# nrf52_breakout_rev_1.net
KiCad netlist of a schematic drawn in EAGLE
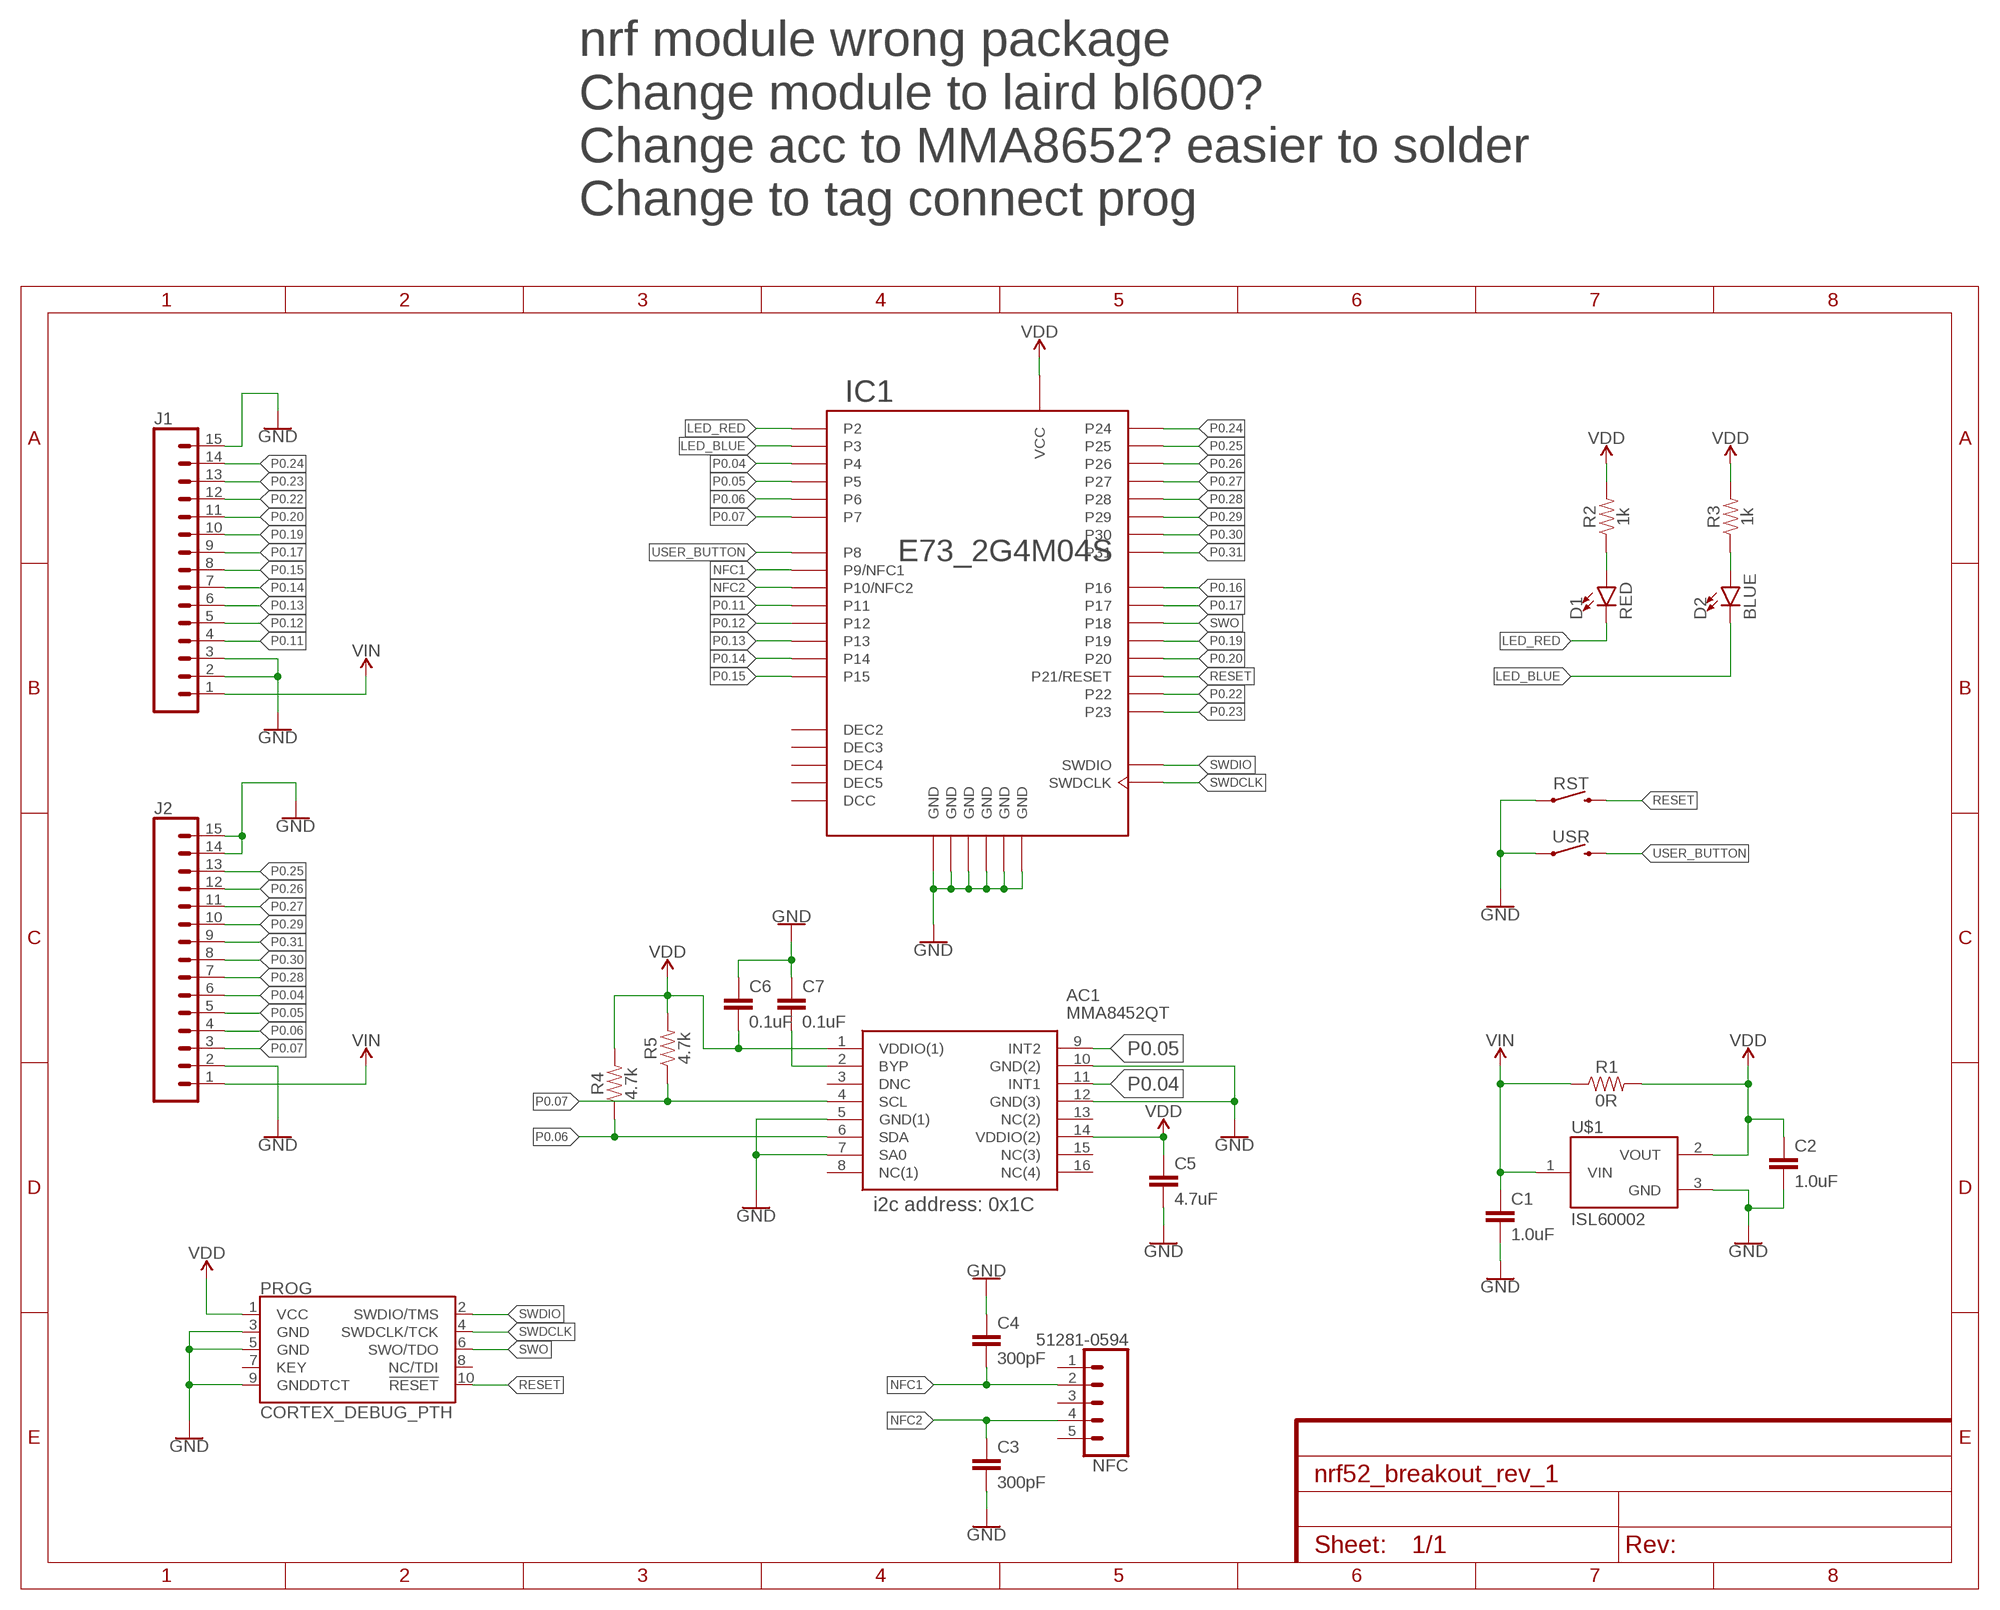
[diagram p0: schematic, sheet 1]

(export (version "E")
  (design (tool "Eeschema 10.0.6"))
  (components
    (comp (ref "AC1")
      (value "MMA8452QT")
      (footprint "eagle-import:PQFN50P300X300X100-16N")
      (fields (field (name "RS_PART_NUMBER") "9227526"))
      (libsource (lib "eagle-import") (part "MMA8452QT"))
    )
    (comp (ref "C1")
      (value "1.0uF")
      (footprint "eagle-import:0603")
      (libsource (lib "eagle-import") (part "1.0UF-0603-16V-10%"))
    )
    (comp (ref "C2")
      (value "1.0uF")
      (footprint "eagle-import:0603")
      (libsource (lib "eagle-import") (part "1.0UF-0603-16V-10%"))
    )
    (comp (ref "C3")
      (value "300pF")
      (footprint "eagle-import:0402")
      (libsource (lib "eagle-import") (part "470NF-0402-16V-10%"))
    )
    (comp (ref "C4")
      (value "300pF")
      (footprint "eagle-import:0402")
      (libsource (lib "eagle-import") (part "470NF-0402-16V-10%"))
    )
    (comp (ref "C5")
      (value "4.7uF")
      (footprint "eagle-import:0603")
      (libsource (lib "eagle-import") (part "4.7UF0603"))
    )
    (comp (ref "C6")
      (value "0.1uF")
      (footprint "eagle-import:0402")
      (libsource (lib "eagle-import") (part "0.1UF-0402-16V-10%"))
    )
    (comp (ref "C7")
      (value "0.1uF")
      (footprint "eagle-import:0402")
      (libsource (lib "eagle-import") (part "0.1UF-0402-16V-10%"))
    )
    (comp (ref "D1")
      (value "RED")
      (footprint "eagle-import:LED-0603")
      (libsource (lib "eagle-import") (part "LED-RED0603"))
    )
    (comp (ref "D2")
      (value "BLUE")
      (footprint "eagle-import:LED-0603")
      (libsource (lib "eagle-import") (part "LED-BLUE0603"))
    )
    (comp (ref "IC1")
      (value "E73_2G4M04S")
      (footprint "eagle-import:E73_2G4M04S")
      (libsource (lib "eagle-import") (part "E73_2G4M04S"))
    )
    (comp (ref "J1")
      (value "CONN_15")
      (footprint "eagle-import:1X15")
      (libsource (lib "eagle-import") (part "CONN_15"))
    )
    (comp (ref "J2")
      (value "CONN_15")
      (footprint "eagle-import:1X15")
      (libsource (lib "eagle-import") (part "CONN_15"))
    )
    (comp (ref "NFC")
      (value "51281-0594")
      (footprint "eagle-import:51281-0594")
      (libsource (lib "eagle-import") (part "51281-0594"))
    )
    (comp (ref "PROG")
      (value "CORTEX_DEBUG_PTH")
      (footprint "eagle-import:2X5-PTH-1.27MM")
      (libsource (lib "eagle-import") (part "CORTEX_DEBUG_PTH"))
    )
    (comp (ref "R1")
      (value "0R")
      (footprint "eagle-import:0603")
      (libsource (lib "eagle-import") (part "RESISTOR0603"))
    )
    (comp (ref "R2")
      (value "1k")
      (footprint "eagle-import:0603")
      (libsource (lib "eagle-import") (part "RESISTOR0603"))
    )
    (comp (ref "R3")
      (value "1k")
      (footprint "eagle-import:0603")
      (libsource (lib "eagle-import") (part "RESISTOR0603"))
    )
    (comp (ref "R4")
      (value "4.7k")
      (footprint "eagle-import:0402")
      (libsource (lib "eagle-import") (part "RESISTOR0402"))
    )
    (comp (ref "R5")
      (value "4.7k")
      (footprint "eagle-import:0402")
      (libsource (lib "eagle-import") (part "RESISTOR0402"))
    )
    (comp (ref "RST")
      (value "MOMENTARY-SWITCH-SPST-SMD-4.6X2.8MM")
      (footprint "eagle-import:TACTILE_SWITCH_SMD_4.6X2.8MM")
      (libsource (lib "eagle-import") (part "MOMENTARY-SWITCH-SPST-SMD-4.6X2.8MM"))
    )
    (comp (ref "U$1")
      (value "ISL60002")
      (footprint "eagle-import:SOT23-3")
      (libsource (lib "eagle-import") (part "ISL60002"))
    )
    (comp (ref "USR")
      (value "MOMENTARY-SWITCH-SPST-SMD-4.6X2.8MM")
      (footprint "eagle-import:TACTILE_SWITCH_SMD_4.6X2.8MM")
      (libsource (lib "eagle-import") (part "MOMENTARY-SWITCH-SPST-SMD-4.6X2.8MM"))
    )
  )
  (nets
    (net (code "1") (name "/DCC") (class "Default")
      (node (ref "IC1") (pin "13") (pinfunction "DCC_13") (pintype "power_in"))
    )
    (net (code "2") (name "/DEC2") (class "Default")
      (node (ref "IC1") (pin "3") (pinfunction "DEC2_3") (pintype "power_in"))
    )
    (net (code "3") (name "/DEC3") (class "Default")
      (node (ref "IC1") (pin "4") (pinfunction "DEC3_4") (pintype "power_in"))
    )
    (net (code "4") (name "/DEC4") (class "Default")
      (node (ref "IC1") (pin "12") (pinfunction "DEC4_12") (pintype "power_in"))
    )
    (net (code "5") (name "/DEC5") (class "Default")
      (node (ref "IC1") (pin "14") (pinfunction "DEC5_14") (pintype "power_in"))
    )
    (net (code "6") (name "GND") (class "Default")
      (node (ref "AC1") (pin "10") (pinfunction "GND(2)_10") (pintype "input"))
      (node (ref "AC1") (pin "12") (pinfunction "GND(3)_12") (pintype "input"))
      (node (ref "AC1") (pin "5") (pinfunction "GND(1)_5") (pintype "input"))
      (node (ref "AC1") (pin "7") (pinfunction "SA0_7") (pintype "input"))
      (node (ref "C1") (pin "2") (pinfunction "2_2") (pintype "passive"))
      (node (ref "C2") (pin "2") (pinfunction "2_2") (pintype "passive"))
      (node (ref "C3") (pin "2") (pinfunction "2_2") (pintype "passive"))
      (node (ref "C4") (pin "1") (pinfunction "1_1") (pintype "passive"))
      (node (ref "C5") (pin "2") (pinfunction "2_2") (pintype "passive"))
      (node (ref "C6") (pin "1") (pinfunction "1_1") (pintype "passive"))
      (node (ref "C7") (pin "1") (pinfunction "1_1") (pintype "passive"))
      (node (ref "IC1") (pin "0") (pinfunction "GND_0") (pintype "bidirectional"))
      (node (ref "IC1") (pin "1") (pinfunction "GND_1") (pintype "bidirectional"))
      (node (ref "IC1") (pin "15") (pinfunction "GND_15") (pintype "bidirectional"))
      (node (ref "IC1") (pin "2") (pinfunction "GND_2") (pintype "bidirectional"))
      (node (ref "IC1") (pin "42") (pinfunction "GND_42") (pintype "bidirectional"))
      (node (ref "IC1") (pin "43") (pinfunction "GND_43") (pintype "bidirectional"))
      (node (ref "J1") (pin "15") (pinfunction "15_15") (pintype "passive"))
      (node (ref "J1") (pin "2") (pinfunction "2_2") (pintype "passive"))
      (node (ref "J1") (pin "3") (pinfunction "3_3") (pintype "passive"))
      (node (ref "J2") (pin "14") (pinfunction "14_14") (pintype "passive"))
      (node (ref "J2") (pin "15") (pinfunction "15_15") (pintype "passive"))
      (node (ref "J2") (pin "2") (pinfunction "2_2") (pintype "passive"))
      (node (ref "PROG") (pin "3") (pinfunction "GND_3") (pintype "bidirectional"))
      (node (ref "PROG") (pin "5") (pinfunction "GND_5") (pintype "bidirectional"))
      (node (ref "PROG") (pin "9") (pinfunction "GNDDTCT_9") (pintype "bidirectional"))
      (node (ref "RST") (pin "1") (pinfunction "1_1") (pintype "passive"))
      (node (ref "RST") (pin "2") (pinfunction "1_2") (pintype "passive"))
      (node (ref "U$1") (pin "3") (pinfunction "GND_3") (pintype "bidirectional"))
      (node (ref "USR") (pin "1") (pinfunction "1_1") (pintype "passive"))
      (node (ref "USR") (pin "2") (pinfunction "1_2") (pintype "passive"))
    )
    (net (code "7") (name "LED_BLUE") (class "Default")
      (node (ref "D2") (pin "C") (pinfunction "C_C") (pintype "passive"))
      (node (ref "IC1") (pin "18") (pinfunction "P3_18") (pintype "bidirectional"))
    )
    (net (code "8") (name "LED_RED") (class "Default")
      (node (ref "D1") (pin "C") (pinfunction "C_C") (pintype "passive"))
      (node (ref "IC1") (pin "17") (pinfunction "P2_17") (pintype "bidirectional"))
    )
    (net (code "9") (name "NFC1") (class "Default")
      (node (ref "C4") (pin "2") (pinfunction "2_2") (pintype "passive"))
      (node (ref "IC1") (pin "24") (pinfunction "P9/NFC1_24") (pintype "bidirectional"))
      (node (ref "NFC") (pin "2") (pinfunction "2_2") (pintype "passive"))
    )
    (net (code "10") (name "NFC2") (class "Default")
      (node (ref "C3") (pin "1") (pinfunction "1_1") (pintype "passive"))
      (node (ref "IC1") (pin "25") (pinfunction "P10/NFC2_25") (pintype "bidirectional"))
      (node (ref "NFC") (pin "4") (pinfunction "4_4") (pintype "passive"))
    )
    (net (code "11") (name "Net-(AC1-BYP)") (class "Default")
      (node (ref "AC1") (pin "2") (pinfunction "BYP_2") (pintype "input"))
      (node (ref "C7") (pin "2") (pinfunction "2_2") (pintype "passive"))
    )
    (net (code "12") (name "Net-(D1-PadA)") (class "Default")
      (node (ref "D1") (pin "A") (pinfunction "A_A") (pintype "passive"))
      (node (ref "R2") (pin "1") (pinfunction "1_1") (pintype "passive"))
    )
    (net (code "13") (name "Net-(D2-PadA)") (class "Default")
      (node (ref "D2") (pin "A") (pinfunction "A_A") (pintype "passive"))
      (node (ref "R3") (pin "1") (pinfunction "1_1") (pintype "passive"))
    )
    (net (code "14") (name "P0.04") (class "Default")
      (node (ref "AC1") (pin "11") (pinfunction "INT1_11") (pintype "input"))
      (node (ref "IC1") (pin "19") (pinfunction "P4_19") (pintype "bidirectional"))
      (node (ref "J2") (pin "6") (pinfunction "6_6") (pintype "passive"))
    )
    (net (code "15") (name "P0.05") (class "Default")
      (node (ref "AC1") (pin "9") (pinfunction "INT2_9") (pintype "input"))
      (node (ref "IC1") (pin "20") (pinfunction "P5_20") (pintype "bidirectional"))
      (node (ref "J2") (pin "5") (pinfunction "5_5") (pintype "passive"))
    )
    (net (code "16") (name "P0.06") (class "Default")
      (node (ref "AC1") (pin "6") (pinfunction "SDA_6") (pintype "input"))
      (node (ref "IC1") (pin "21") (pinfunction "P6_21") (pintype "bidirectional"))
      (node (ref "J2") (pin "4") (pinfunction "4_4") (pintype "passive"))
      (node (ref "R4") (pin "1") (pinfunction "1_1") (pintype "passive"))
    )
    (net (code "17") (name "P0.07") (class "Default")
      (node (ref "AC1") (pin "4") (pinfunction "SCL_4") (pintype "input"))
      (node (ref "IC1") (pin "22") (pinfunction "P7_22") (pintype "bidirectional"))
      (node (ref "J2") (pin "3") (pinfunction "3_3") (pintype "passive"))
      (node (ref "R5") (pin "1") (pinfunction "1_1") (pintype "passive"))
    )
    (net (code "18") (name "P0.11") (class "Default")
      (node (ref "IC1") (pin "26") (pinfunction "P11_26") (pintype "bidirectional"))
      (node (ref "J1") (pin "4") (pinfunction "4_4") (pintype "passive"))
    )
    (net (code "19") (name "P0.12") (class "Default")
      (node (ref "IC1") (pin "27") (pinfunction "P12_27") (pintype "bidirectional"))
      (node (ref "J1") (pin "5") (pinfunction "5_5") (pintype "passive"))
    )
    (net (code "20") (name "P0.13") (class "Default")
      (node (ref "IC1") (pin "28") (pinfunction "P13_28") (pintype "bidirectional"))
      (node (ref "J1") (pin "6") (pinfunction "6_6") (pintype "passive"))
    )
    (net (code "21") (name "P0.14") (class "Default")
      (node (ref "IC1") (pin "29") (pinfunction "P14_29") (pintype "bidirectional"))
      (node (ref "J1") (pin "7") (pinfunction "7_7") (pintype "passive"))
    )
    (net (code "22") (name "P0.15") (class "Default")
      (node (ref "IC1") (pin "30") (pinfunction "P15_30") (pintype "bidirectional"))
      (node (ref "J1") (pin "8") (pinfunction "8_8") (pintype "passive"))
    )
    (net (code "23") (name "P0.16") (class "Default")
      (node (ref "IC1") (pin "31") (pinfunction "P16_31") (pintype "bidirectional"))
    )
    (net (code "24") (name "P0.17") (class "Default")
      (node (ref "IC1") (pin "32") (pinfunction "P17_32") (pintype "bidirectional"))
      (node (ref "J1") (pin "9") (pinfunction "9_9") (pintype "passive"))
    )
    (net (code "25") (name "P0.19") (class "Default")
      (node (ref "IC1") (pin "34") (pinfunction "P19_34") (pintype "bidirectional"))
      (node (ref "J1") (pin "10") (pinfunction "10_10") (pintype "passive"))
    )
    (net (code "26") (name "P0.20") (class "Default")
      (node (ref "IC1") (pin "35") (pinfunction "P20_35") (pintype "bidirectional"))
      (node (ref "J1") (pin "11") (pinfunction "11_11") (pintype "passive"))
    )
    (net (code "27") (name "P0.22") (class "Default")
      (node (ref "IC1") (pin "39") (pinfunction "P22_39") (pintype "bidirectional"))
      (node (ref "J1") (pin "12") (pinfunction "12_12") (pintype "passive"))
    )
    (net (code "28") (name "P0.23") (class "Default")
      (node (ref "IC1") (pin "40") (pinfunction "P23_40") (pintype "bidirectional"))
      (node (ref "J1") (pin "13") (pinfunction "13_13") (pintype "passive"))
    )
    (net (code "29") (name "P0.24") (class "Default")
      (node (ref "IC1") (pin "41") (pinfunction "P24_41") (pintype "bidirectional"))
      (node (ref "J1") (pin "14") (pinfunction "14_14") (pintype "passive"))
    )
    (net (code "30") (name "P0.25") (class "Default")
      (node (ref "IC1") (pin "5") (pinfunction "P25_5") (pintype "bidirectional"))
      (node (ref "J2") (pin "13") (pinfunction "13_13") (pintype "passive"))
    )
    (net (code "31") (name "P0.26") (class "Default")
      (node (ref "IC1") (pin "6") (pinfunction "P26_6") (pintype "bidirectional"))
      (node (ref "J2") (pin "12") (pinfunction "12_12") (pintype "passive"))
    )
    (net (code "32") (name "P0.27") (class "Default")
      (node (ref "IC1") (pin "7") (pinfunction "P27_7") (pintype "bidirectional"))
      (node (ref "J2") (pin "11") (pinfunction "11_11") (pintype "passive"))
    )
    (net (code "33") (name "P0.28") (class "Default")
      (node (ref "IC1") (pin "8") (pinfunction "P28_8") (pintype "bidirectional"))
      (node (ref "J2") (pin "7") (pinfunction "7_7") (pintype "passive"))
    )
    (net (code "34") (name "P0.29") (class "Default")
      (node (ref "IC1") (pin "9") (pinfunction "P29_9") (pintype "bidirectional"))
      (node (ref "J2") (pin "10") (pinfunction "10_10") (pintype "passive"))
    )
    (net (code "35") (name "P0.30") (class "Default")
      (node (ref "IC1") (pin "10") (pinfunction "P30_10") (pintype "bidirectional"))
      (node (ref "J2") (pin "8") (pinfunction "8_8") (pintype "passive"))
    )
    (net (code "36") (name "P0.31") (class "Default")
      (node (ref "IC1") (pin "11") (pinfunction "P31_11") (pintype "bidirectional"))
      (node (ref "J2") (pin "9") (pinfunction "9_9") (pintype "passive"))
    )
    (net (code "37") (name "RESET") (class "Default")
      (node (ref "IC1") (pin "36") (pinfunction "P21/RESET_36") (pintype "bidirectional"))
      (node (ref "PROG") (pin "10") (pinfunction "~{RESET}_10") (pintype "bidirectional"))
      (node (ref "RST") (pin "3") (pinfunction "2_3") (pintype "passive"))
      (node (ref "RST") (pin "4") (pinfunction "2_4") (pintype "passive"))
    )
    (net (code "38") (name "SWDCLK") (class "Default")
      (node (ref "IC1") (pin "37") (pinfunction "SWDCLK_37") (pintype "input"))
      (node (ref "PROG") (pin "4") (pinfunction "SWDCLK/TCK_4") (pintype "bidirectional"))
    )
    (net (code "39") (name "SWDIO") (class "Default")
      (node (ref "IC1") (pin "38") (pinfunction "SWDIO_38") (pintype "bidirectional"))
      (node (ref "PROG") (pin "2") (pinfunction "SWDIO/TMS_2") (pintype "bidirectional"))
    )
    (net (code "40") (name "SWO") (class "Default")
      (node (ref "IC1") (pin "33") (pinfunction "P18_33") (pintype "bidirectional"))
      (node (ref "PROG") (pin "6") (pinfunction "SWO/TDO_6") (pintype "bidirectional"))
    )
    (net (code "41") (name "USER_BUTTON") (class "Default")
      (node (ref "IC1") (pin "23") (pinfunction "P8_23") (pintype "bidirectional"))
      (node (ref "USR") (pin "3") (pinfunction "2_3") (pintype "passive"))
      (node (ref "USR") (pin "4") (pinfunction "2_4") (pintype "passive"))
    )
    (net (code "42") (name "VDD") (class "Default")
      (node (ref "AC1") (pin "1") (pinfunction "VDDIO(1)_1") (pintype "input"))
      (node (ref "AC1") (pin "14") (pinfunction "VDDIO(2)_14") (pintype "input"))
      (node (ref "C2") (pin "1") (pinfunction "1_1") (pintype "passive"))
      (node (ref "C5") (pin "1") (pinfunction "1_1") (pintype "passive"))
      (node (ref "C6") (pin "2") (pinfunction "2_2") (pintype "passive"))
      (node (ref "IC1") (pin "16") (pinfunction "VCC_16") (pintype "passive"))
      (node (ref "PROG") (pin "1") (pinfunction "VCC_1") (pintype "bidirectional"))
      (node (ref "R1") (pin "2") (pinfunction "2_2") (pintype "passive"))
      (node (ref "R2") (pin "2") (pinfunction "2_2") (pintype "passive"))
      (node (ref "R3") (pin "2") (pinfunction "2_2") (pintype "passive"))
      (node (ref "R4") (pin "2") (pinfunction "2_2") (pintype "passive"))
      (node (ref "R5") (pin "2") (pinfunction "2_2") (pintype "passive"))
      (node (ref "U$1") (pin "2") (pinfunction "VOUT_2") (pintype "bidirectional"))
    )
    (net (code "43") (name "VIN") (class "Default")
      (node (ref "C1") (pin "1") (pinfunction "1_1") (pintype "passive"))
      (node (ref "J1") (pin "1") (pinfunction "1_1") (pintype "passive"))
      (node (ref "J2") (pin "1") (pinfunction "1_1") (pintype "passive"))
      (node (ref "R1") (pin "1") (pinfunction "1_1") (pintype "passive"))
      (node (ref "U$1") (pin "1") (pinfunction "VIN_1") (pintype "bidirectional"))
    )
    (net (code "44") (name "unconnected-(AC1-DNC-Pad3)") (class "Default")
      (node (ref "AC1") (pin "3") (pinfunction "DNC_3") (pintype "input"))
    )
    (net (code "45") (name "unconnected-(AC1-NC(1)-Pad8)") (class "Default")
      (node (ref "AC1") (pin "8") (pinfunction "NC(1)_8") (pintype "input"))
    )
    (net (code "46") (name "unconnected-(AC1-NC(2)-Pad13)") (class "Default")
      (node (ref "AC1") (pin "13") (pinfunction "NC(2)_13") (pintype "input"))
    )
    (net (code "47") (name "unconnected-(AC1-NC(3)-Pad15)") (class "Default")
      (node (ref "AC1") (pin "15") (pinfunction "NC(3)_15") (pintype "input"))
    )
    (net (code "48") (name "unconnected-(AC1-NC(4)-Pad16)") (class "Default")
      (node (ref "AC1") (pin "16") (pinfunction "NC(4)_16") (pintype "input"))
    )
    (net (code "49") (name "unconnected-(NFC-Pad1)") (class "Default")
      (node (ref "NFC") (pin "1") (pinfunction "1_1") (pintype "passive"))
    )
    (net (code "50") (name "unconnected-(NFC-Pad3)") (class "Default")
      (node (ref "NFC") (pin "3") (pinfunction "3_3") (pintype "passive"))
    )
    (net (code "51") (name "unconnected-(NFC-Pad5)") (class "Default")
      (node (ref "NFC") (pin "5") (pinfunction "5_5") (pintype "passive"))
    )
    (net (code "52") (name "unconnected-(PROG-KEY-Pad7)") (class "Default")
      (node (ref "PROG") (pin "7") (pinfunction "KEY_7") (pintype "bidirectional"))
    )
    (net (code "53") (name "unconnected-(PROG-NC{slash}TDI-Pad8)") (class "Default")
      (node (ref "PROG") (pin "8") (pinfunction "NC/TDI_8") (pintype "bidirectional"))
    )
  )
)
